# 01_Connector.net
KiCad netlist of a schematic drawn in Altium Designer
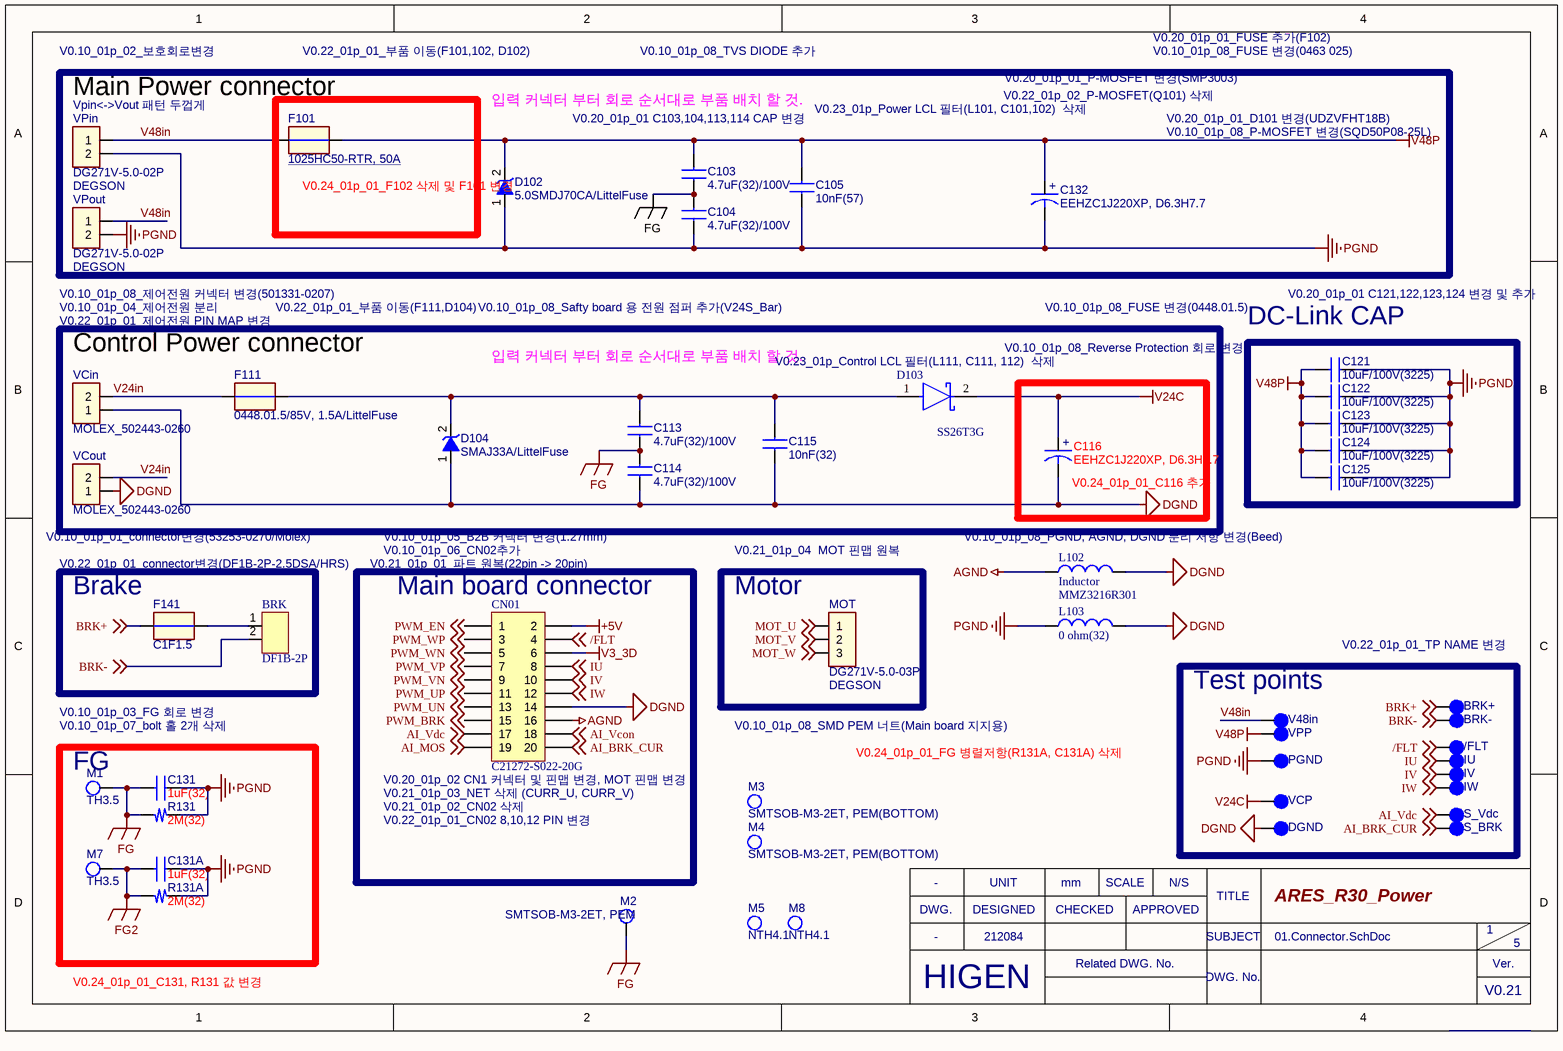
[diagram p0: 01.Connector.SchDoc]

(export (version "E")
  (design (tool "Eeschema 10.0.6"))
  (components
    (comp (ref "/FLT")
      (value "TP")
      (footprint "TP-SMD")
      (libsource (lib "*") (part "2H_TestPointThroughHole"))
    )
    (comp (ref "BRK")
      (value "DF1B-2P")
      (footprint "DF1B-2P-2.5DSA")
      (libsource (lib "DF1BB") (part "Component_1"))
    )
    (comp (ref "BRK+")
      (value "TP")
      (footprint "TP-SMD")
      (libsource (lib "*") (part "2H_TestPointThroughHole"))
    )
    (comp (ref "BRK-")
      (value "TP")
      (footprint "TP-SMD")
      (libsource (lib "*") (part "2H_TestPointThroughHole"))
    )
    (comp (ref "C103")
      (value "4.7uF(32)/100V")
      (footprint "C-3216")
      (libsource (lib "HIGEN") (part "Cap_NP"))
    )
    (comp (ref "C104")
      (value "4.7uF(32)/100V")
      (footprint "C-3216")
      (libsource (lib "HIGEN") (part "Cap_NP"))
    )
    (comp (ref "C105") (value "10nF(57)") (footprint "C-5750") (libsource (lib "HIGEN") (part "Cap_NP")))
    (comp (ref "C113")
      (value "4.7uF(32)/100V")
      (footprint "C-3216")
      (libsource (lib "HIGEN") (part "Cap_NP"))
    )
    (comp (ref "C114")
      (value "4.7uF(32)/100V")
      (footprint "C-3216")
      (libsource (lib "HIGEN") (part "Cap_NP"))
    )
    (comp (ref "C115") (value "10nF(32)") (footprint "C-3216S") (libsource (lib "HIGEN") (part "Cap_NP")))
    (comp (ref "C116")
      (value "EEHZC1J220XP, D6.3H7.7")
      (footprint "EC-F80")
      (libsource (lib "HIGEN") (part "CAP_Pol"))
    )
    (comp (ref "C121")
      (value "10uF/100V(3225)")
      (footprint "C-3225")
      (libsource (lib "HIGEN") (part "Cap_NP"))
    )
    (comp (ref "C122")
      (value "10uF/100V(3225)")
      (footprint "C-3225")
      (libsource (lib "HIGEN") (part "Cap_NP"))
    )
    (comp (ref "C123")
      (value "10uF/100V(3225)")
      (footprint "C-3225")
      (libsource (lib "HIGEN") (part "Cap_NP"))
    )
    (comp (ref "C124")
      (value "10uF/100V(3225)")
      (footprint "C-3225")
      (libsource (lib "HIGEN") (part "Cap_NP"))
    )
    (comp (ref "C125")
      (value "10uF/100V(3225)")
      (footprint "C-3225")
      (libsource (lib "HIGEN") (part "Cap_NP"))
    )
    (comp (ref "C131") (value "1uF(32)") (footprint "C-3216S") (libsource (lib "HIGEN") (part "Cap_NP")))
    (comp (ref "C131A") (value "1uF(32)") (footprint "C-3216S") (libsource (lib "HIGEN") (part "Cap_NP")))
    (comp (ref "C132")
      (value "EEHZC1J220XP, D6.3H7.7")
      (footprint "EC-F80")
      (libsource (lib "HIGEN") (part "CAP_Pol"))
    )
    (comp (ref "CN01")
      (value "C21272-S022-20G")
      (footprint "PH08SMD-D20P_PWR")
      (description "Header, 10-Pin, Dual row")
      (fields (field (name "PUBLISHER") "Altium Limited"))
      (libsource (lib "Miscellaneous Connectors") (part "Header 10X2"))
    )
    (comp (ref "D102")
      (value "5.0SMDJ70CA/LittelFuse")
      (footprint "DO-214AB")
      (libsource (lib "HIGEN") (part "Diode_TVS"))
    )
    (comp (ref "D103")
      (value "SS26T3G")
      (footprint "DO-214AA")
      (description "DIODE SCHOTTKY 60V 2A SMB")
      (fields
        (field (name "3DS PART NUMBER") "417-00001")
        (field (name "DIGIKEY PART NUMBER") "SS26T3GOSCT-ND")
      )
      (libsource (lib "EEConcierge") (part "SS26T3G"))
    )
    (comp (ref "D104")
      (value "SMAJ33A/LittelFuse")
      (footprint "SMA")
      (libsource (lib "HIGEN") (part "Diode_TVS"))
    )
    (comp (ref "DGND")
      (value "TP")
      (footprint "TP-SMD")
      (libsource (lib "*") (part "2H_TestPointThroughHole"))
    )
    (comp (ref "F101")
      (value "1025HC50-RTR, 50A")
      (footprint "FUSE-SMT_1025HC50-RTR_50A")
      (libsource (lib "HIGEN") (part "Fuse"))
    )
    (comp (ref "F111")
      (value "0448.01.5/85V, 1.5A/LittelFuse")
      (footprint "0448.005")
      (libsource (lib "HIGEN") (part "Fuse"))
    )
    (comp (ref "F141") (value "C1F1.5") (footprint "C-3216") (libsource (lib "") (part "Fuse_1")))
    (comp (ref "IU") (value "TP") (footprint "TP-SMD") (libsource (lib "*") (part "2H_TestPointThroughHole")))
    (comp (ref "IV") (value "TP") (footprint "TP-SMD") (libsource (lib "*") (part "2H_TestPointThroughHole")))
    (comp (ref "IW") (value "TP") (footprint "TP-SMD") (libsource (lib "*") (part "2H_TestPointThroughHole")))
    (comp (ref "L102")
      (value "Inductor")
      (footprint "L-3216")
      (fields (field (name "ALTIUM_VALUE") "MMZ3216R301") (field (name "PUBLISHER") "Altium Limited"))
      (libsource (lib "Miscellaneous Devices") (part "Inductor"))
    )
    (comp (ref "L103")
      (value "0 ohm(32)")
      (footprint "L-3216")
      (description "Inductor")
      (fields (field (name "PUBLISHER") "Altium Limited"))
      (libsource (lib "Miscellaneous Devices") (part "Inductor"))
    )
    (comp (ref "M1") (value "TH3.5") (footprint "MH-3.5MM") (libsource (lib "HIGEN") (part "ThroughHole")))
    (comp (ref "M2")
      (value "SMTSOB-M3-2ET, PEM")
      (footprint "SMTSOB-M3-2")
      (libsource (lib "HIGEN") (part "ThroughHole"))
    )
    (comp (ref "M3")
      (value "SMTSOB-M3-2ET, PEM(BOTTOM)")
      (footprint "SMTSOB-M3-2_BOT")
      (libsource (lib "") (part "ThroughHole_2"))
    )
    (comp (ref "M4")
      (value "SMTSOB-M3-2ET, PEM(BOTTOM)")
      (footprint "SMTSOB-M3-2_BOT")
      (libsource (lib "") (part "ThroughHole_1"))
    )
    (comp (ref "M5") (value "NTH4.1") (footprint "NTH4.1") (libsource (lib "") (part "ThroughHole_1")))
    (comp (ref "M7") (value "TH3.5") (footprint "MH-3.5MM") (libsource (lib "HIGEN") (part "ThroughHole")))
    (comp (ref "M8") (value "NTH4.1") (footprint "NTH4.1") (libsource (lib "") (part "ThroughHole_1")))
    (comp (ref "MOT")
      (value "DG271V-5.0-03P")
      (footprint "DG271V-5.0-03P")
      (libsource (lib "HIGEN") (part "Connector_1x3"))
    )
    (comp (ref "PGND")
      (value "TP")
      (footprint "TP-SMD")
      (libsource (lib "*") (part "2H_TestPointThroughHole"))
    )
    (comp (ref "R131")
      (value "2M(32)")
      (footprint "R-3216S")
      (libsource (lib "AM437X_MAIN_LOW") (part "Res"))
    )
    (comp (ref "R131A")
      (value "2M(32)")
      (footprint "R-3216S")
      (libsource (lib "AM437X_MAIN_LOW") (part "Res"))
    )
    (comp (ref "S_BRK")
      (value "TP")
      (footprint "TP-SMD")
      (libsource (lib "*") (part "2H_TestPointThroughHole"))
    )
    (comp (ref "S_Vdc")
      (value "TP")
      (footprint "TP-SMD")
      (libsource (lib "*") (part "2H_TestPointThroughHole"))
    )
    (comp (ref "V48in")
      (value "TP")
      (footprint "TP-SMD")
      (libsource (lib "*") (part "2H_TestPointThroughHole"))
    )
    (comp (ref "VCin")
      (value "MOLEX_502443-0260")
      (footprint "MOLEX_502443-0260")
      (libsource (lib "") (part "Connector_1x2_1"))
    )
    (comp (ref "VCout")
      (value "MOLEX_502443-0260")
      (footprint "MOLEX_502443-0260")
      (libsource (lib "") (part "Connector_1x2_1"))
    )
    (comp (ref "VCP")
      (value "TP")
      (footprint "TP-SMD")
      (libsource (lib "*") (part "2H_TestPointThroughHole"))
    )
    (comp (ref "VPin")
      (value "DG271V-5.0-02P")
      (footprint "DG271V-5.0-02P")
      (libsource (lib "HIGEN") (part "Connector_1x2"))
    )
    (comp (ref "VPout")
      (value "DG271V-5.0-02P")
      (footprint "DG271V-5.0-02P")
      (libsource (lib "HIGEN") (part "Connector_1x2"))
    )
    (comp (ref "VPP")
      (value "TP")
      (footprint "TP-SMD")
      (libsource (lib "*") (part "2H_TestPointThroughHole"))
    )
  )
  (nets
    (net (code "1") (name "+5V") (class "Default")
      (node (ref "CN01") (pin "2") (pinfunction "2_2") (pintype "passive"))
    )
    (net (code "2") (name "/V24in") (class "Default")
      (node (ref "F111") (pin "1") (pinfunction "1_1") (pintype "passive"))
      (node (ref "VCin") (pin "2") (pinfunction "2_2") (pintype "passive"))
      (node (ref "VCout") (pin "2") (pinfunction "2_2") (pintype "passive"))
    )
    (net (code "3") (name "/V48in") (class "Default")
      (node (ref "F101") (pin "1") (pinfunction "1_1") (pintype "passive"))
      (node (ref "V48in") (pin "1") (pinfunction "1_1") (pintype "passive"))
      (node (ref "VPin") (pin "1") (pinfunction "1_1") (pintype "passive"))
      (node (ref "VPout") (pin "1") (pinfunction "1_1") (pintype "passive"))
    )
    (net (code "4") (name "AGND") (class "Default")
      (node (ref "CN01") (pin "16") (pinfunction "16_16") (pintype "passive"))
      (node (ref "L102") (pin "1") (pinfunction "1_1") (pintype "passive"))
    )
    (net (code "5") (name "AI_BRK_CUR") (class "Default")
      (node (ref "CN01") (pin "20") (pinfunction "20_20") (pintype "passive"))
      (node (ref "S_BRK") (pin "1") (pinfunction "1_1") (pintype "passive"))
    )
    (net (code "6") (name "AI_MOS") (class "Default")
      (node (ref "CN01") (pin "19") (pinfunction "19_19") (pintype "passive"))
    )
    (net (code "7") (name "AI_Vcon") (class "Default")
      (node (ref "CN01") (pin "18") (pinfunction "18_18") (pintype "passive"))
    )
    (net (code "8") (name "AI_Vdc") (class "Default")
      (node (ref "CN01") (pin "17") (pinfunction "17_17") (pintype "passive"))
      (node (ref "S_Vdc") (pin "1") (pinfunction "1_1") (pintype "passive"))
    )
    (net (code "9") (name "BRK+") (class "Default")
      (node (ref "BRK+") (pin "1") (pinfunction "1_1") (pintype "passive"))
      (node (ref "F141") (pin "2") (pinfunction "2_2") (pintype "passive"))
    )
    (net (code "10") (name "BRK-") (class "Default")
      (node (ref "BRK") (pin "2") (pinfunction "2_2") (pintype "passive"))
      (node (ref "BRK-") (pin "1") (pinfunction "1_1") (pintype "passive"))
    )
    (net (code "11") (name "DGND") (class "Default")
      (node (ref "C114") (pin "1") (pinfunction "1_1") (pintype "passive"))
      (node (ref "C115") (pin "1") (pinfunction "1_1") (pintype "passive"))
      (node (ref "C116") (pin "2") (pinfunction "2_2") (pintype "passive"))
      (node (ref "CN01") (pin "14") (pinfunction "14_14") (pintype "passive"))
      (node (ref "D104") (pin "1") (pinfunction "A_1") (pintype "passive"))
      (node (ref "DGND") (pin "1") (pinfunction "1_1") (pintype "passive"))
      (node (ref "L102") (pin "2") (pinfunction "2_2") (pintype "passive"))
      (node (ref "L103") (pin "2") (pinfunction "2_2") (pintype "passive"))
      (node (ref "VCin") (pin "1") (pinfunction "1_1") (pintype "passive"))
      (node (ref "VCout") (pin "1") (pinfunction "1_1") (pintype "passive"))
    )
    (net (code "12") (name "FG") (class "Default")
      (node (ref "C103") (pin "1") (pinfunction "1_1") (pintype "passive"))
      (node (ref "C104") (pin "2") (pinfunction "2_2") (pintype "passive"))
      (node (ref "C113") (pin "1") (pinfunction "1_1") (pintype "passive"))
      (node (ref "C114") (pin "2") (pinfunction "2_2") (pintype "passive"))
      (node (ref "C131") (pin "1") (pinfunction "1_1") (pintype "passive"))
      (node (ref "M1") (pin "1") (pinfunction "TP_1") (pintype "passive"))
      (node (ref "M2") (pin "1") (pinfunction "TP_1") (pintype "passive"))
      (node (ref "R131") (pin "1") (pinfunction "P1_1") (pintype "passive"))
    )
    (net (code "13") (name "FG2") (class "Default")
      (node (ref "C131A") (pin "1") (pinfunction "1_1") (pintype "passive"))
      (node (ref "M7") (pin "1") (pinfunction "TP_1") (pintype "passive"))
      (node (ref "R131A") (pin "1") (pinfunction "P1_1") (pintype "passive"))
    )
    (net (code "14") (name "IU") (class "Default")
      (node (ref "CN01") (pin "8") (pinfunction "8_8") (pintype "passive"))
      (node (ref "IU") (pin "1") (pinfunction "1_1") (pintype "passive"))
    )
    (net (code "15") (name "IV") (class "Default")
      (node (ref "CN01") (pin "10") (pinfunction "10_10") (pintype "passive"))
      (node (ref "IV") (pin "1") (pinfunction "1_1") (pintype "passive"))
    )
    (net (code "16") (name "IW") (class "Default")
      (node (ref "CN01") (pin "12") (pinfunction "12_12") (pintype "passive"))
      (node (ref "IW") (pin "1") (pinfunction "1_1") (pintype "passive"))
    )
    (net (code "17") (name "MOT_U") (class "Default")
      (node (ref "MOT") (pin "1") (pinfunction "1_1") (pintype "passive"))
    )
    (net (code "18") (name "MOT_V") (class "Default")
      (node (ref "MOT") (pin "2") (pinfunction "2_2") (pintype "passive"))
    )
    (net (code "19") (name "MOT_W") (class "Default")
      (node (ref "MOT") (pin "3") (pinfunction "3_3") (pintype "passive"))
    )
    (net (code "20") (name "Net-(BRK-2-Pad1)") (class "Default")
      (node (ref "BRK") (pin "1") (pinfunction "2_1") (pintype "passive"))
      (node (ref "F141") (pin "1") (pinfunction "1_1") (pintype "passive"))
    )
    (net (code "21") (name "Net-(D103-A)") (class "Default")
      (node (ref "C113") (pin "2") (pinfunction "2_2") (pintype "passive"))
      (node (ref "C115") (pin "2") (pinfunction "2_2") (pintype "passive"))
      (node (ref "D103") (pin "1") (pinfunction "A_1") (pintype "passive"))
      (node (ref "D104") (pin "2") (pinfunction "K_2") (pintype "passive"))
      (node (ref "F111") (pin "2") (pinfunction "2_2") (pintype "passive"))
    )
    (net (code "22") (name "PGND") (class "Default")
      (node (ref "C104") (pin "1") (pinfunction "1_1") (pintype "passive"))
      (node (ref "C105") (pin "1") (pinfunction "1_1") (pintype "passive"))
      (node (ref "C121") (pin "2") (pinfunction "2_2") (pintype "passive"))
      (node (ref "C122") (pin "2") (pinfunction "2_2") (pintype "passive"))
      (node (ref "C123") (pin "2") (pinfunction "2_2") (pintype "passive"))
      (node (ref "C124") (pin "2") (pinfunction "2_2") (pintype "passive"))
      (node (ref "C125") (pin "2") (pinfunction "2_2") (pintype "passive"))
      (node (ref "C131") (pin "2") (pinfunction "2_2") (pintype "passive"))
      (node (ref "C131A") (pin "2") (pinfunction "2_2") (pintype "passive"))
      (node (ref "C132") (pin "2") (pinfunction "2_2") (pintype "passive"))
      (node (ref "D102") (pin "1") (pinfunction "A_1") (pintype "passive"))
      (node (ref "L103") (pin "1") (pinfunction "1_1") (pintype "passive"))
      (node (ref "PGND") (pin "1") (pinfunction "1_1") (pintype "passive"))
      (node (ref "R131") (pin "2") (pinfunction "P2_2") (pintype "passive"))
      (node (ref "R131A") (pin "2") (pinfunction "P2_2") (pintype "passive"))
      (node (ref "VPin") (pin "2") (pinfunction "2_2") (pintype "passive"))
      (node (ref "VPout") (pin "2") (pinfunction "2_2") (pintype "passive"))
    )
    (net (code "23") (name "PWM_BRK") (class "Default")
      (node (ref "CN01") (pin "15") (pinfunction "15_15") (pintype "passive"))
    )
    (net (code "24") (name "PWM_EN") (class "Default")
      (node (ref "CN01") (pin "1") (pinfunction "1_1") (pintype "passive"))
    )
    (net (code "25") (name "PWM_UN") (class "Default")
      (node (ref "CN01") (pin "13") (pinfunction "13_13") (pintype "passive"))
    )
    (net (code "26") (name "PWM_UP") (class "Default")
      (node (ref "CN01") (pin "11") (pinfunction "11_11") (pintype "passive"))
    )
    (net (code "27") (name "PWM_VN") (class "Default")
      (node (ref "CN01") (pin "9") (pinfunction "9_9") (pintype "passive"))
    )
    (net (code "28") (name "PWM_VP") (class "Default")
      (node (ref "CN01") (pin "7") (pinfunction "7_7") (pintype "passive"))
    )
    (net (code "29") (name "PWM_WN") (class "Default")
      (node (ref "CN01") (pin "5") (pinfunction "5_5") (pintype "passive"))
    )
    (net (code "30") (name "PWM_WP") (class "Default")
      (node (ref "CN01") (pin "3") (pinfunction "3_3") (pintype "passive"))
    )
    (net (code "31") (name "TP") (class "Default")
      (node (ref "M3") (pin "1") (pinfunction "TP_1") (pintype "power_in"))
    )
    (net (code "32") (name "V3_3D") (class "Default")
      (node (ref "CN01") (pin "6") (pinfunction "6_6") (pintype "passive"))
    )
    (net (code "33") (name "V24C") (class "Default")
      (node (ref "C116") (pin "1") (pinfunction "1_1") (pintype "passive"))
      (node (ref "D103") (pin "2") (pinfunction "C_2") (pintype "passive"))
      (node (ref "VCP") (pin "1") (pinfunction "1_1") (pintype "passive"))
    )
    (net (code "34") (name "V48P") (class "Default")
      (node (ref "C103") (pin "2") (pinfunction "2_2") (pintype "passive"))
      (node (ref "C105") (pin "2") (pinfunction "2_2") (pintype "passive"))
      (node (ref "C121") (pin "1") (pinfunction "1_1") (pintype "passive"))
      (node (ref "C122") (pin "1") (pinfunction "1_1") (pintype "passive"))
      (node (ref "C123") (pin "1") (pinfunction "1_1") (pintype "passive"))
      (node (ref "C124") (pin "1") (pinfunction "1_1") (pintype "passive"))
      (node (ref "C125") (pin "1") (pinfunction "1_1") (pintype "passive"))
      (node (ref "C132") (pin "1") (pinfunction "1_1") (pintype "passive"))
      (node (ref "D102") (pin "2") (pinfunction "K_2") (pintype "passive"))
      (node (ref "F101") (pin "2") (pinfunction "2_2") (pintype "passive"))
      (node (ref "VPP") (pin "1") (pinfunction "1_1") (pintype "passive"))
    )
    (net (code "35") (name "unconnected-(M4-TP-Pad1)") (class "Default")
      (node (ref "M4") (pin "1") (pinfunction "TP_1") (pintype "passive"))
    )
    (net (code "36") (name "unconnected-(M5-TP-Pad1)") (class "Default")
      (node (ref "M5") (pin "1") (pinfunction "TP_1") (pintype "passive"))
    )
    (net (code "37") (name "unconnected-(M8-TP-Pad1)") (class "Default")
      (node (ref "M8") (pin "1") (pinfunction "TP_1") (pintype "passive"))
    )
    (net (code "38") (name "{slash}FLT") (class "Default")
      (node (ref "/FLT") (pin "1") (pinfunction "1_1") (pintype "passive"))
      (node (ref "CN01") (pin "4") (pinfunction "4_4") (pintype "passive"))
    )
  )
)
